# sheet_solider.net
KiCad netlist of a schematic drawn in Altium Designer
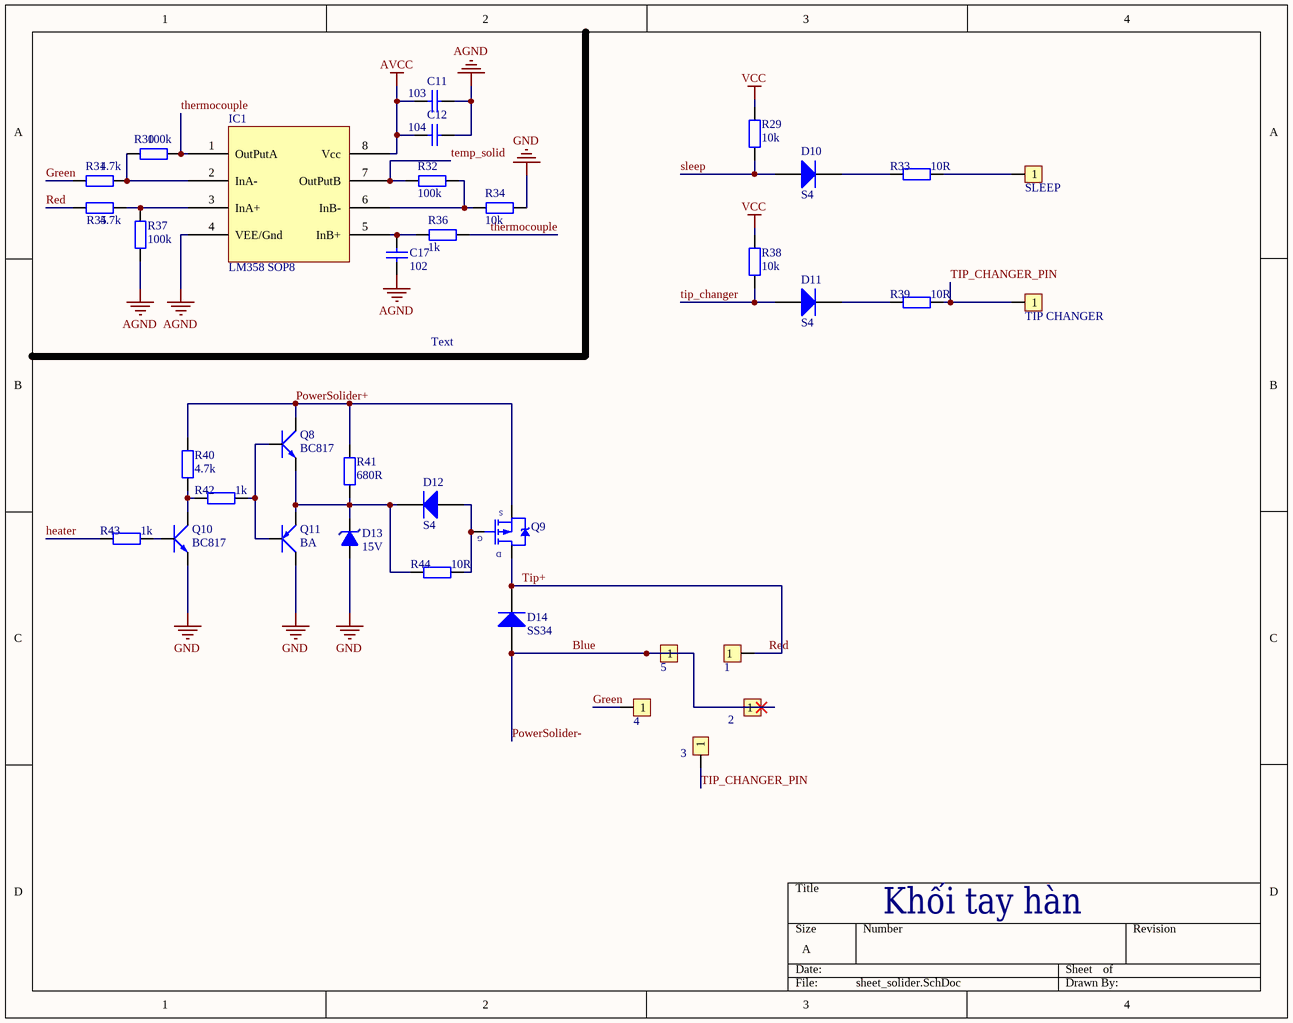
[diagram p0: sheet_solider.SchDoc]

(export (version "E")
  (design (tool "Eeschema 10.0.6"))
  (components
    (comp (ref "C11")
      (value "103")
      (footprint "tu 0603")
      (description "Dán")
      (libsource (lib "Altium_Lib_by_KhueNguyenCreator") (part "Tu 0603 106 16V 20%"))
    )
    (comp (ref "C12")
      (value "104")
      (footprint "tu 0603")
      (description "Dán")
      (libsource (lib "Altium_Lib_by_KhueNguyenCreator") (part "Tu 0603 106 16V 20%"))
    )
    (comp (ref "C17")
      (value "102")
      (footprint "tu 0603")
      (description "Dán")
      (libsource (lib "Altium_Lib_by_KhueNguyenCreator") (part "Tu 0603 106 16V 20%"))
    )
    (comp (ref "D10")
      (value "S4")
      (footprint "DIODE SOD-123")
      (description "Dán")
      (libsource (lib "Driver4.0_Project_Fix_source_5V") (part "Diode S4"))
    )
    (comp (ref "D11")
      (value "S4")
      (footprint "DIODE SOD-123")
      (description "Dán")
      (libsource (lib "Driver4.0_Project_Fix_source_5V") (part "Diode S4"))
    )
    (comp (ref "D12")
      (value "S4")
      (footprint "DIODE SOD-123")
      (description "Dán")
      (libsource (lib "Altium_Lib_by_KhueNguyenCreator") (part "Diode S4"))
    )
    (comp (ref "D13")
      (value "15V")
      (footprint "DIODE ZENNER SMD SOD80")
      (description "Dán")
      (libsource (lib "Altium_Lib_by_KhueNguyenCreator") (part "Diode Zener 15V"))
    )
    (comp (ref "D14")
      (value "SS34")
      (footprint "DIODE SMA")
      (description "Dán")
      (libsource (lib "Altium_Lib_by_KhueNguyenCreator") (part "Diode SS34 ( 1N5822 )"))
    )
    (comp (ref "IC1")
      (value "LM358 SOP8")
      (footprint "SOP 8")
      (description "Dán")
      (libsource (lib "Altium_Lib_by_KhueNguyenCreator") (part "LM358 SOP8"))
    )
    (comp (ref "JP3")
      (value "SLEEP")
      (footprint "JP 1x1 DT")
      (description "Cắm")
      (libsource (lib "") (part "JP 1x1 2.54 Duc Cong_1"))
    )
    (comp (ref "JP4")
      (value "TIP CHANGER")
      (footprint "JP 1x1 DT")
      (description "Cắm")
      (libsource (lib "") (part "JP 1x1 2.54 Duc Cong_1"))
    )
    (comp (ref "JP5")
      (value "5")
      (footprint "JP 1x1 DT")
      (description "Cắm")
      (libsource (lib "") (part "JP 1x1 2.54 Duc Cong_1"))
    )
    (comp (ref "JP6")
      (value "1")
      (footprint "JP 1x1 DT")
      (description "Cắm")
      (libsource (lib "") (part "JP 1x1 2.54 Duc Cong_2"))
    )
    (comp (ref "JP7")
      (value "4")
      (footprint "JP 1x1 DT")
      (description "Cắm")
      (libsource (lib "") (part "JP 1x1 2.54 Duc Cong_1"))
    )
    (comp (ref "JP8")
      (value "2")
      (footprint "JP 1x1 DT")
      (description "Cắm")
      (libsource (lib "") (part "JP 1x1 2.54 Duc Cong_2"))
    )
    (comp (ref "JP9")
      (value "3")
      (footprint "JP 1x1 DT")
      (description "Cắm")
      (libsource (lib "Altium_Lib_by_KhueNguyenCreator") (part "JP 1x1 2.54 Duc Cong"))
    )
    (comp (ref "Q8")
      (value "BC817")
      (footprint "SOT-23")
      (description "SOT-23 - C8658")
      (libsource (lib "Altium_Lib_by_KhueNguyenCreator") (part "Trans BC817"))
    )
    (comp (ref "Q9")
      (value "IRF4905S")
      (footprint "D2PACK")
      (description "55V 75A")
      (libsource (lib "Driver4.0_Project_Fix_source_5V") (part "IRF4905S"))
    )
    (comp (ref "Q10")
      (value "BC817")
      (footprint "SOT-23")
      (description "SOT-23 - C8658")
      (libsource (lib "Altium_Lib_by_KhueNguyenCreator") (part "Trans BC817"))
    )
    (comp (ref "Q11")
      (value "BA")
      (footprint "SOT23")
      (description "PNP 600mW, ECB")
      (libsource (lib "Altium_Lib_by_KhueNguyenCreator") (part "Trans A1015 BA SMD"))
    )
    (comp (ref "R29")
      (value "10k")
      (footprint "Tro smd 0603")
      (description "Dán")
      (libsource (lib "Altium_Lib_by_KhueNguyenCreator") (part "Tro 0603 5% 10R"))
    )
    (comp (ref "R30")
      (value "100k")
      (footprint "Tro smd 0603")
      (description "Dán")
      (libsource (lib "Altium_Lib_by_KhueNguyenCreator") (part "Tro 0603 5% 10R"))
    )
    (comp (ref "R31")
      (value "4.7k")
      (footprint "Tro smd 0603")
      (description "Dán")
      (libsource (lib "Altium_Lib_by_KhueNguyenCreator") (part "Tro 0603 5% 10R"))
    )
    (comp (ref "R32")
      (value "100k")
      (footprint "Tro smd 0603")
      (description "Dán")
      (libsource (lib "Altium_Lib_by_KhueNguyenCreator") (part "Tro 0603 5% 10R"))
    )
    (comp (ref "R33")
      (value "10R")
      (footprint "Tro smd 0603")
      (description "Dán")
      (libsource (lib "Altium_Lib_by_KhueNguyenCreator") (part "Tro 0603 5% 10R"))
    )
    (comp (ref "R34")
      (value "10k")
      (footprint "Tro smd 0603")
      (description "Dán")
      (libsource (lib "Altium_Lib_by_KhueNguyenCreator") (part "Tro 0603 5% 10R"))
    )
    (comp (ref "R35")
      (value "4.7k")
      (footprint "Tro smd 0603")
      (description "Dán")
      (libsource (lib "Altium_Lib_by_KhueNguyenCreator") (part "Tro 0603 5% 10R"))
    )
    (comp (ref "R36")
      (value "1k")
      (footprint "Tro smd 0603")
      (description "Dán")
      (libsource (lib "Altium_Lib_by_KhueNguyenCreator") (part "Tro 0603 5% 10R"))
    )
    (comp (ref "R37")
      (value "100k")
      (footprint "Tro smd 0603")
      (description "Dán")
      (libsource (lib "Altium_Lib_by_KhueNguyenCreator") (part "Tro 0603 5% 10R"))
    )
    (comp (ref "R38")
      (value "10k")
      (footprint "Tro smd 0603")
      (description "Dán")
      (libsource (lib "Altium_Lib_by_KhueNguyenCreator") (part "Tro 0603 5% 10R"))
    )
    (comp (ref "R39")
      (value "10R")
      (footprint "Tro smd 0603")
      (description "Dán")
      (libsource (lib "Altium_Lib_by_KhueNguyenCreator") (part "Tro 0603 5% 10R"))
    )
    (comp (ref "R40")
      (value "4.7k")
      (footprint "Tro smd 0603")
      (description "Dán")
      (libsource (lib "Altium_Lib_by_KhueNguyenCreator") (part "Tro 0603 5% 10R"))
    )
    (comp (ref "R41")
      (value "680R")
      (footprint "tro vach 1/4w")
      (description "Cắm")
      (libsource (lib "Altium_Lib_by_KhueNguyenCreator") (part "Tro Vach 1/4W 5% 680R"))
    )
    (comp (ref "R42")
      (value "1k")
      (footprint "Tro smd 0603")
      (description "Dán")
      (libsource (lib "Altium_Lib_by_KhueNguyenCreator") (part "Tro 0603 5% 10R"))
    )
    (comp (ref "R43")
      (value "1k")
      (footprint "Tro smd 0603")
      (description "Dán")
      (libsource (lib "Altium_Lib_by_KhueNguyenCreator") (part "Tro 0603 5% 10R"))
    )
    (comp (ref "R44")
      (value "10R")
      (footprint "Tro smd 0603")
      (description "Dán")
      (libsource (lib "Altium_Lib_by_KhueNguyenCreator") (part "Tro 0603 5% 10R"))
    )
  )
  (nets
    (net (code "1") (name "/Blue") (class "Default")
      (node (ref "D14") (pin "1") (pinfunction "A_1") (pintype "passive"))
      (node (ref "JP5") (pin "1") (pinfunction "1_1") (pintype "passive"))
      (node (ref "JP8") (pin "1") (pinfunction "1_1") (pintype "passive"))
    )
    (net (code "2") (name "/Green") (class "Default")
      (node (ref "JP7") (pin "1") (pinfunction "1_1") (pintype "passive"))
      (node (ref "R31") (pin "2") (pinfunction "2_2") (pintype "passive"))
    )
    (net (code "3") (name "/PowerSolider+") (class "Default")
      (node (ref "Q8") (pin "3") (pinfunction "C_3") (pintype "passive"))
      (node (ref "Q9") (pin "3") (pinfunction "S_3") (pintype "passive"))
      (node (ref "R40") (pin "2") (pinfunction "2_2") (pintype "passive"))
      (node (ref "R41") (pin "2") (pinfunction "2_2") (pintype "passive"))
    )
    (net (code "4") (name "/Red") (class "Default")
      (node (ref "D14") (pin "2") (pinfunction "K_2") (pintype "passive"))
      (node (ref "JP6") (pin "1") (pinfunction "1_1") (pintype "passive"))
      (node (ref "Q9") (pin "2") (pinfunction "D_2") (pintype "passive"))
      (node (ref "R35") (pin "2") (pinfunction "2_2") (pintype "passive"))
    )
    (net (code "5") (name "/TIP_CHANGER_PIN") (class "Default")
      (node (ref "JP4") (pin "1") (pinfunction "1_1") (pintype "passive"))
      (node (ref "JP9") (pin "1") (pinfunction "1_1") (pintype "passive"))
      (node (ref "R39") (pin "2") (pinfunction "2_2") (pintype "passive"))
    )
    (net (code "6") (name "/heater") (class "Default")
      (node (ref "R43") (pin "1") (pinfunction "1_1") (pintype "passive"))
    )
    (net (code "7") (name "/sleep") (class "Default")
      (node (ref "D10") (pin "1") (pinfunction "A_1") (pintype "passive"))
      (node (ref "R29") (pin "1") (pinfunction "1_1") (pintype "passive"))
    )
    (net (code "8") (name "/temp_solid") (class "Default")
      (node (ref "IC1") (pin "7") (pinfunction "OutPutB_7") (pintype "passive"))
      (node (ref "R32") (pin "1") (pinfunction "1_1") (pintype "passive"))
    )
    (net (code "9") (name "/thermocouple") (class "Default")
      (node (ref "IC1") (pin "1") (pinfunction "OutPutA_1") (pintype "passive"))
      (node (ref "R30") (pin "2") (pinfunction "2_2") (pintype "passive"))
      (node (ref "R36") (pin "1") (pinfunction "1_1") (pintype "passive"))
    )
    (net (code "10") (name "/tip_changer") (class "Default")
      (node (ref "D11") (pin "1") (pinfunction "A_1") (pintype "passive"))
      (node (ref "R38") (pin "1") (pinfunction "1_1") (pintype "passive"))
    )
    (net (code "11") (name "AGND") (class "Default")
      (node (ref "C11") (pin "2") (pinfunction "2_2") (pintype "passive"))
      (node (ref "C12") (pin "2") (pinfunction "2_2") (pintype "passive"))
      (node (ref "C17") (pin "1") (pinfunction "1_1") (pintype "passive"))
      (node (ref "IC1") (pin "4") (pinfunction "VEE/Gnd_4") (pintype "passive"))
      (node (ref "R37") (pin "2") (pinfunction "2_2") (pintype "passive"))
    )
    (net (code "12") (name "AVCC") (class "Default")
      (node (ref "C11") (pin "1") (pinfunction "1_1") (pintype "passive"))
      (node (ref "C12") (pin "1") (pinfunction "1_1") (pintype "passive"))
      (node (ref "IC1") (pin "8") (pinfunction "Vcc_8") (pintype "passive"))
    )
    (net (code "13") (name "GND") (class "Default")
      (node (ref "D13") (pin "1") (pinfunction "A_1") (pintype "passive"))
      (node (ref "Q10") (pin "2") (pinfunction "E_2") (pintype "passive"))
      (node (ref "Q11") (pin "3") (pinfunction "C_3") (pintype "passive"))
      (node (ref "R34") (pin "2") (pinfunction "2_2") (pintype "passive"))
    )
    (net (code "14") (name "Net-(D10-K)") (class "Default")
      (node (ref "D10") (pin "2") (pinfunction "K_2") (pintype "passive"))
      (node (ref "R33") (pin "1") (pinfunction "1_1") (pintype "passive"))
    )
    (net (code "15") (name "Net-(D11-K)") (class "Default")
      (node (ref "D11") (pin "2") (pinfunction "K_2") (pintype "passive"))
      (node (ref "R39") (pin "1") (pinfunction "1_1") (pintype "passive"))
    )
    (net (code "16") (name "Net-(D12-A)") (class "Default")
      (node (ref "D12") (pin "1") (pinfunction "A_1") (pintype "passive"))
      (node (ref "Q9") (pin "1") (pinfunction "G_1") (pintype "passive"))
      (node (ref "R44") (pin "2") (pinfunction "2_2") (pintype "passive"))
    )
    (net (code "17") (name "Net-(D12-K)") (class "Default")
      (node (ref "D12") (pin "2") (pinfunction "K_2") (pintype "passive"))
      (node (ref "D13") (pin "2") (pinfunction "K_2") (pintype "passive"))
      (node (ref "Q11") (pin "2") (pinfunction "E_2") (pintype "passive"))
      (node (ref "Q8") (pin "2") (pinfunction "E_2") (pintype "passive"))
      (node (ref "R41") (pin "1") (pinfunction "1_1") (pintype "passive"))
      (node (ref "R44") (pin "1") (pinfunction "1_1") (pintype "passive"))
    )
    (net (code "18") (name "Net-(IC1-InA+)") (class "Default")
      (node (ref "IC1") (pin "3") (pinfunction "InA+_3") (pintype "passive"))
      (node (ref "R35") (pin "1") (pinfunction "1_1") (pintype "passive"))
      (node (ref "R37") (pin "1") (pinfunction "1_1") (pintype "passive"))
    )
    (net (code "19") (name "Net-(IC1-InA-)") (class "Default")
      (node (ref "IC1") (pin "2") (pinfunction "InA-_2") (pintype "passive"))
      (node (ref "R30") (pin "1") (pinfunction "1_1") (pintype "passive"))
      (node (ref "R31") (pin "1") (pinfunction "1_1") (pintype "passive"))
    )
    (net (code "20") (name "Net-(IC1-InB+)") (class "Default")
      (node (ref "C17") (pin "2") (pinfunction "2_2") (pintype "passive"))
      (node (ref "IC1") (pin "5") (pinfunction "InB+_5") (pintype "passive"))
      (node (ref "R36") (pin "2") (pinfunction "2_2") (pintype "passive"))
    )
    (net (code "21") (name "Net-(IC1-InB-)") (class "Default")
      (node (ref "IC1") (pin "6") (pinfunction "InB-_6") (pintype "passive"))
      (node (ref "R32") (pin "2") (pinfunction "2_2") (pintype "passive"))
      (node (ref "R34") (pin "1") (pinfunction "1_1") (pintype "passive"))
    )
    (net (code "22") (name "Net-(JP3-Pad1)") (class "Default")
      (node (ref "JP3") (pin "1") (pinfunction "1_1") (pintype "passive"))
      (node (ref "R33") (pin "2") (pinfunction "2_2") (pintype "passive"))
    )
    (net (code "23") (name "Net-(Q10-B)") (class "Default")
      (node (ref "Q10") (pin "1") (pinfunction "B_1") (pintype "passive"))
      (node (ref "R43") (pin "2") (pinfunction "2_2") (pintype "passive"))
    )
    (net (code "24") (name "Net-(Q10-C)") (class "Default")
      (node (ref "Q10") (pin "3") (pinfunction "C_3") (pintype "passive"))
      (node (ref "R40") (pin "1") (pinfunction "1_1") (pintype "passive"))
      (node (ref "R42") (pin "1") (pinfunction "1_1") (pintype "passive"))
    )
    (net (code "25") (name "Net-(Q11-B)") (class "Default")
      (node (ref "Q11") (pin "1") (pinfunction "B_1") (pintype "passive"))
      (node (ref "Q8") (pin "1") (pinfunction "B_1") (pintype "passive"))
      (node (ref "R42") (pin "2") (pinfunction "2_2") (pintype "passive"))
    )
    (net (code "26") (name "VCC") (class "Default")
      (node (ref "R29") (pin "2") (pinfunction "2_2") (pintype "passive"))
      (node (ref "R38") (pin "2") (pinfunction "2_2") (pintype "passive"))
    )
  )
)
